# Nano_pro.net
KiCad netlist of a schematic drawn in Altium Designer
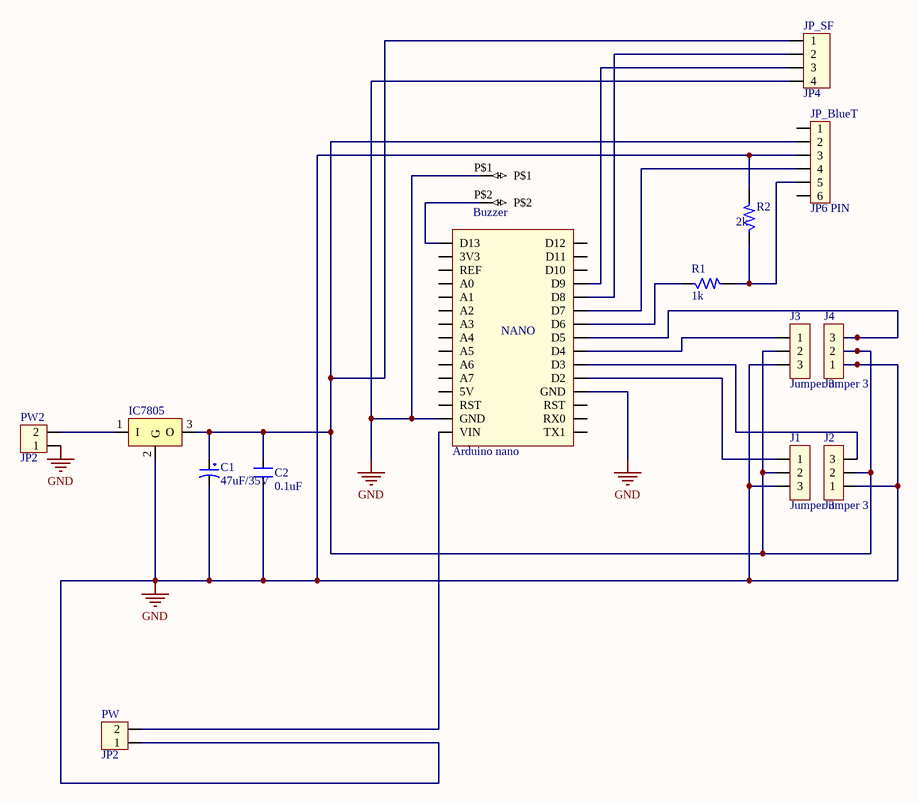
[diagram p0: Nano_pro.SchDoc]

(export (version "E")
  (design (tool "Eeschema 10.0.6"))
  (components
    (comp (ref "Arduino nano")
      (value "Arduino Nano")
      (footprint "Arduino Nano")
      (description "Arduino NANO")
      (libsource (lib "LIBRARYALT (1)") (part "Arduino Nano"))
    )
    (comp (ref "Buzzer")
      (value "PT-1340P-P10-PQ")
      (footprint "*PT-1340_PT-1340P-P10-PQ(Primary)")
      (libsource (lib "PT-1340P-P10-PQ") (part "PT-1340P-P10-PQ"))
    )
    (comp (ref "C1")
      (value "47uF/35V")
      (footprint "CP1.5/3.4")
      (description "Cap 100uF/35V - 470uF/16V")
      (libsource (lib "echipkool-com-library") (part "CP3"))
    )
    (comp (ref "C2")
      (value "0.1uF")
      (footprint "SM-CAP-0805")
      (description "Cap SMD")
      (libsource (lib "echipkool-com-library") (part "CM"))
    )
    (comp (ref "IC7805")
      (value "LM78xx")
      (footprint "TO220NH")
      (description "Positive Voltage Regulator")
      (fields (field (name "PUBLISHER") "Altium Limited"))
      (libsource (lib "LIBRARYALT (1)") (part "LM78xx"))
    )
    (comp (ref "J1") (value "Jumper 3") (footprint "CON3") (libsource (lib "") (part "JP3_1")))
    (comp (ref "J2")
      (value "Jumper 3")
      (footprint "CON3")
      (libsource (lib "echipkool-com-library") (part "JP3"))
    )
    (comp (ref "J3") (value "Jumper 3") (footprint "CON3") (libsource (lib "") (part "JP3_1")))
    (comp (ref "J4")
      (value "Jumper 3")
      (footprint "CON3")
      (libsource (lib "echipkool-com-library") (part "JP3"))
    )
    (comp (ref "JP_BlueT")
      (value "JP6 PIN")
      (footprint "CON6")
      (libsource (lib "echipkool-com-library") (part "JP6"))
    )
    (comp (ref "JP_SF")
      (value "JP4")
      (footprint "CON4")
      (description "Connector 4")
      (libsource (lib "echipkool-com-library") (part "Con4"))
    )
    (comp (ref "PW")
      (value "JP2")
      (footprint "CON2")
      (description "Connector 2")
      (libsource (lib "echipkool-com-library") (part "Con2"))
    )
    (comp (ref "PW2")
      (value "JP2")
      (footprint "CON2")
      (description "Connector 2")
      (libsource (lib "echipkool-com-library") (part "Con2"))
    )
    (comp (ref "R1")
      (value "1k")
      (footprint "SM-RES-0805")
      (description "Resistor 1/4W")
      (libsource (lib "echipkool-com-library") (part "R"))
    )
    (comp (ref "R2")
      (value "2k")
      (footprint "SM-RES-0805")
      (description "Resistor 1/4W")
      (libsource (lib "echipkool-com-library") (part "R"))
    )
  )
  (nets
    (net (code "1") (name "GND") (class "Default")
      (node (ref "Arduino nano") (pin "GND") (pinfunction "GND_GND") (pintype "passive"))
      (node (ref "Buzzer") (pin "P$1") (pinfunction "P$1_P$1") (pintype "bidirectional"))
      (node (ref "C1") (pin "2") (pinfunction "2_2") (pintype "passive"))
      (node (ref "C2") (pin "1") (pinfunction "1_1") (pintype "passive"))
      (node (ref "IC7805") (pin "2") (pinfunction "G_2") (pintype "power_in"))
      (node (ref "J1") (pin "3") (pinfunction "3_3") (pintype "passive"))
      (node (ref "J2") (pin "1") (pinfunction "1_1") (pintype "passive"))
      (node (ref "J3") (pin "3") (pinfunction "3_3") (pintype "passive"))
      (node (ref "J4") (pin "1") (pinfunction "1_1") (pintype "passive"))
      (node (ref "JP_BlueT") (pin "3") (pinfunction "3_3") (pintype "passive"))
      (node (ref "JP_SF") (pin "4") (pinfunction "4_4") (pintype "passive"))
      (node (ref "PW") (pin "1") (pinfunction "1_1") (pintype "passive"))
      (node (ref "PW2") (pin "1") (pinfunction "1_1") (pintype "passive"))
      (node (ref "R2") (pin "2") (pinfunction "2_2") (pintype "passive"))
    )
    (net (code "2") (name "Net-(Arduino nano-PadD2)") (class "Default")
      (node (ref "Arduino nano") (pin "D2") (pinfunction "D2_D2") (pintype "passive"))
      (node (ref "J1") (pin "1") (pinfunction "1_1") (pintype "passive"))
    )
    (net (code "3") (name "Net-(Arduino nano-PadD3)") (class "Default")
      (node (ref "Arduino nano") (pin "D3") (pinfunction "D3_D3") (pintype "passive"))
      (node (ref "J2") (pin "3") (pinfunction "3_3") (pintype "passive"))
    )
    (net (code "4") (name "Net-(Arduino nano-PadD4)") (class "Default")
      (node (ref "Arduino nano") (pin "D4") (pinfunction "D4_D4") (pintype "passive"))
      (node (ref "J3") (pin "1") (pinfunction "1_1") (pintype "passive"))
    )
    (net (code "5") (name "Net-(Arduino nano-PadD5)") (class "Default")
      (node (ref "Arduino nano") (pin "D5") (pinfunction "D5_D5") (pintype "passive"))
      (node (ref "J4") (pin "3") (pinfunction "3_3") (pintype "passive"))
    )
    (net (code "6") (name "Net-(Arduino nano-PadD6)") (class "Default")
      (node (ref "Arduino nano") (pin "D6") (pinfunction "D6_D6") (pintype "passive"))
      (node (ref "R1") (pin "1") (pinfunction "1_1") (pintype "passive"))
    )
    (net (code "7") (name "Net-(Arduino nano-PadD7)") (class "Default")
      (node (ref "Arduino nano") (pin "D7") (pinfunction "D7_D7") (pintype "passive"))
      (node (ref "JP_BlueT") (pin "4") (pinfunction "4_4") (pintype "passive"))
    )
    (net (code "8") (name "Net-(Arduino nano-PadD8)") (class "Default")
      (node (ref "Arduino nano") (pin "D8") (pinfunction "D8_D8") (pintype "passive"))
      (node (ref "JP_SF") (pin "2") (pinfunction "2_2") (pintype "passive"))
    )
    (net (code "9") (name "Net-(Arduino nano-PadD9)") (class "Default")
      (node (ref "Arduino nano") (pin "D9") (pinfunction "D9_D9") (pintype "passive"))
      (node (ref "JP_SF") (pin "3") (pinfunction "3_3") (pintype "passive"))
    )
    (net (code "10") (name "Net-(Arduino nano-PadD13)") (class "Default")
      (node (ref "Arduino nano") (pin "D13") (pinfunction "D13_D13") (pintype "passive"))
      (node (ref "Buzzer") (pin "P$2") (pinfunction "P$2_P$2") (pintype "bidirectional"))
    )
    (net (code "11") (name "Net-(Arduino nano-PadVIN)") (class "Default")
      (node (ref "Arduino nano") (pin "VIN") (pinfunction "VIN_VIN") (pintype "passive"))
      (node (ref "PW") (pin "2") (pinfunction "2_2") (pintype "passive"))
    )
    (net (code "12") (name "Net-(IC7805-I)") (class "Default")
      (node (ref "IC7805") (pin "1") (pinfunction "I_1") (pintype "power_in"))
      (node (ref "PW2") (pin "2") (pinfunction "2_2") (pintype "passive"))
    )
    (net (code "13") (name "Net-(IC7805-O)") (class "Default")
      (node (ref "C1") (pin "1") (pinfunction "1_1") (pintype "passive"))
      (node (ref "C2") (pin "2") (pinfunction "2_2") (pintype "passive"))
      (node (ref "IC7805") (pin "3") (pinfunction "O_3") (pintype "power_in"))
      (node (ref "J1") (pin "2") (pinfunction "2_2") (pintype "passive"))
      (node (ref "J2") (pin "2") (pinfunction "2_2") (pintype "passive"))
      (node (ref "J3") (pin "2") (pinfunction "2_2") (pintype "passive"))
      (node (ref "J4") (pin "2") (pinfunction "2_2") (pintype "passive"))
      (node (ref "JP_BlueT") (pin "2") (pinfunction "2_2") (pintype "passive"))
      (node (ref "JP_SF") (pin "1") (pinfunction "1_1") (pintype "passive"))
    )
    (net (code "14") (name "Net-(JP_BlueT-Pad5)") (class "Default")
      (node (ref "JP_BlueT") (pin "5") (pinfunction "5_5") (pintype "passive"))
      (node (ref "R1") (pin "2") (pinfunction "2_2") (pintype "passive"))
      (node (ref "R2") (pin "1") (pinfunction "1_1") (pintype "passive"))
    )
    (net (code "15") (name "unconnected-(Arduino nano-Pad3V3)") (class "Default")
      (node (ref "Arduino nano") (pin "3V3") (pinfunction "3V3_3V3") (pintype "passive"))
    )
    (net (code "16") (name "unconnected-(Arduino nano-Pad5V)") (class "Default")
      (node (ref "Arduino nano") (pin "5V") (pinfunction "5V_5V") (pintype "passive"))
    )
    (net (code "17") (name "unconnected-(Arduino nano-PadA0)") (class "Default")
      (node (ref "Arduino nano") (pin "A0") (pinfunction "A0_A0") (pintype "passive"))
    )
    (net (code "18") (name "unconnected-(Arduino nano-PadA1)") (class "Default")
      (node (ref "Arduino nano") (pin "A1") (pinfunction "A1_A1") (pintype "passive"))
    )
    (net (code "19") (name "unconnected-(Arduino nano-PadA2)") (class "Default")
      (node (ref "Arduino nano") (pin "A2") (pinfunction "A2_A2") (pintype "passive"))
    )
    (net (code "20") (name "unconnected-(Arduino nano-PadA3)") (class "Default")
      (node (ref "Arduino nano") (pin "A3") (pinfunction "A3_A3") (pintype "passive"))
    )
    (net (code "21") (name "unconnected-(Arduino nano-PadA4)") (class "Default")
      (node (ref "Arduino nano") (pin "A4") (pinfunction "A4_A4") (pintype "passive"))
    )
    (net (code "22") (name "unconnected-(Arduino nano-PadA5)") (class "Default")
      (node (ref "Arduino nano") (pin "A5") (pinfunction "A5_A5") (pintype "passive"))
    )
    (net (code "23") (name "unconnected-(Arduino nano-PadA6)") (class "Default")
      (node (ref "Arduino nano") (pin "A6") (pinfunction "A6_A6") (pintype "passive"))
    )
    (net (code "24") (name "unconnected-(Arduino nano-PadA7)") (class "Default")
      (node (ref "Arduino nano") (pin "A7") (pinfunction "A7_A7") (pintype "passive"))
    )
    (net (code "25") (name "unconnected-(Arduino nano-PadD10)") (class "Default")
      (node (ref "Arduino nano") (pin "D10") (pinfunction "D10_D10") (pintype "passive"))
    )
    (net (code "26") (name "unconnected-(Arduino nano-PadD11)") (class "Default")
      (node (ref "Arduino nano") (pin "D11") (pinfunction "D11_D11") (pintype "passive"))
    )
    (net (code "27") (name "unconnected-(Arduino nano-PadD12)") (class "Default")
      (node (ref "Arduino nano") (pin "D12") (pinfunction "D12_D12") (pintype "passive"))
    )
    (net (code "28") (name "unconnected-(Arduino nano-PadREF)") (class "Default")
      (node (ref "Arduino nano") (pin "REF") (pinfunction "REF_REF") (pintype "passive"))
    )
    (net (code "29") (name "unconnected-(Arduino nano-PadRST)") (class "Default")
      (node (ref "Arduino nano") (pin "RST") (pinfunction "RST_RST") (pintype "passive"))
    )
    (net (code "30") (name "unconnected-(Arduino nano-PadRST)_1") (class "Default")
      (node (ref "Arduino nano") (pin "RST") (pinfunction "RST_RST") (pintype "passive"))
    )
    (net (code "31") (name "unconnected-(Arduino nano-PadRX0)") (class "Default")
      (node (ref "Arduino nano") (pin "RX0") (pinfunction "RX0_RX0") (pintype "passive"))
    )
    (net (code "32") (name "unconnected-(Arduino nano-PadTX1)") (class "Default")
      (node (ref "Arduino nano") (pin "TX1") (pinfunction "TX1_TX1") (pintype "passive"))
    )
    (net (code "33") (name "unconnected-(JP_BlueT-Pad1)") (class "Default")
      (node (ref "JP_BlueT") (pin "1") (pinfunction "1_1") (pintype "passive"))
    )
    (net (code "34") (name "unconnected-(JP_BlueT-Pad6)") (class "Default")
      (node (ref "JP_BlueT") (pin "6") (pinfunction "6_6") (pintype "passive"))
    )
  )
)
